# 327final.net
KiCad netlist of a schematic drawn in EAGLE
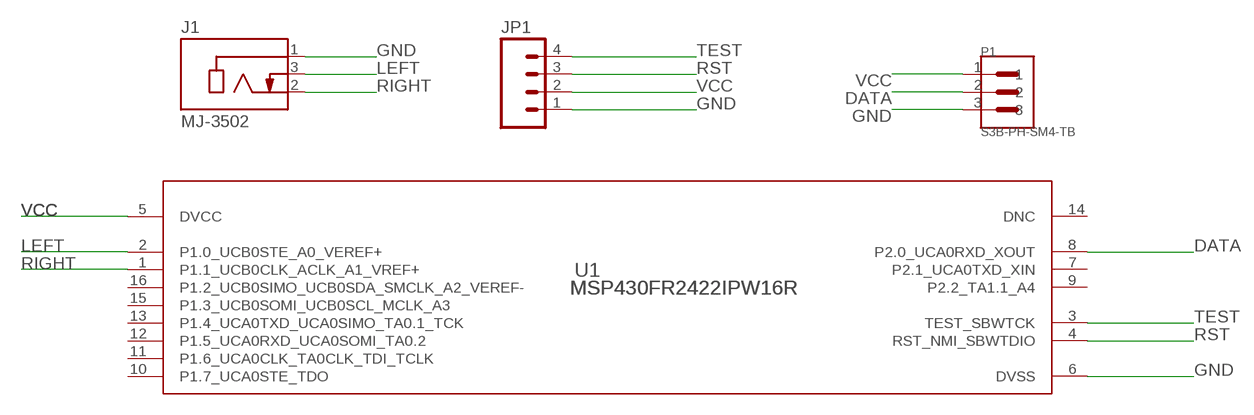
[diagram p0: schematic, sheet 1]

(export (version "E")
  (design (tool "Eeschema 10.0.6"))
  (components
    (comp (ref "J1")
      (value "MJ-3502")
      (footprint "eagle-import:CUI_MJ-3502")
      (fields (field (name "MANUFACTURER") "CUI INC"))
      (libsource (lib "eagle-import") (part "MJ-3502"))
    )
    (comp (ref "JP1")
      (value "HEADER_1X04LOCK")
      (footprint "eagle-import:1X04_LOCK")
      (libsource (lib "eagle-import") (part "HEADER_1X04LOCK"))
    )
    (comp (ref "P1")
      (value "S3B-PH-SM4-TB")
      (footprint "eagle-import:JST_S3B-PH-SM4-TB")
      (fields (field (name "MF") "JST"))
      (libsource (lib "eagle-import") (part "S3B-PH-SM4-TB"))
    )
    (comp (ref "U1")
      (value "MSP430FR2422IPW16R")
      (footprint "eagle-import:PW0016A_N")
      (fields (field (name "COPYRIGHT") "Copyright (C) 2023 Ultra Librarian. All rights reserved."))
      (libsource (lib "eagle-import") (part "MSP430FR2422IPW16R"))
    )
  )
  (nets
    (net (code "1") (name "/DATA") (class "Default")
      (node (ref "P1") (pin "2") (pinfunction "2_2") (pintype "passive"))
      (node (ref "U1") (pin "8") (pinfunction "P2.0_UCA0RXD_XOUT_8") (pintype "bidirectional"))
    )
    (net (code "2") (name "/DNC") (class "Default")
      (node (ref "U1") (pin "14") (pinfunction "DNC_14") (pintype "power_in"))
    )
    (net (code "3") (name "/GND") (class "Default")
      (node (ref "J1") (pin "1") (pinfunction "1_1") (pintype "passive"))
      (node (ref "JP1") (pin "1") (pinfunction "1_1") (pintype "passive"))
      (node (ref "P1") (pin "3") (pinfunction "3_3") (pintype "passive"))
      (node (ref "U1") (pin "6") (pinfunction "DVSS_6") (pintype "power_in"))
    )
    (net (code "4") (name "/LEFT") (class "Default")
      (node (ref "J1") (pin "3") (pinfunction "3_3") (pintype "passive"))
      (node (ref "U1") (pin "2") (pinfunction "P1.0_UCB0STE_A0_VEREF+_2") (pintype "bidirectional"))
    )
    (net (code "5") (name "/RIGHT") (class "Default")
      (node (ref "J1") (pin "2") (pinfunction "2_2") (pintype "passive"))
      (node (ref "U1") (pin "1") (pinfunction "P1.1_UCB0CLK_ACLK_A1_VREF+_1") (pintype "bidirectional"))
    )
    (net (code "6") (name "/RST") (class "Default")
      (node (ref "JP1") (pin "3") (pinfunction "3_3") (pintype "passive"))
      (node (ref "U1") (pin "4") (pinfunction "RST_NMI_SBWTDIO_4") (pintype "bidirectional"))
    )
    (net (code "7") (name "/TEST") (class "Default")
      (node (ref "JP1") (pin "4") (pinfunction "4_4") (pintype "passive"))
      (node (ref "U1") (pin "3") (pinfunction "TEST_SBWTCK_3") (pintype "input"))
    )
    (net (code "8") (name "/VCC") (class "Default")
      (node (ref "JP1") (pin "2") (pinfunction "2_2") (pintype "passive"))
      (node (ref "P1") (pin "1") (pinfunction "1_1") (pintype "passive"))
      (node (ref "U1") (pin "5") (pinfunction "DVCC_5") (pintype "power_in"))
    )
    (net (code "9") (name "unconnected-(U1-P1.2_UCB0SIMO_UCB0SDA_SMCLK_A2_VEREF--Pad16)") (class "Default")
      (node (ref "U1") (pin "16") (pinfunction "P1.2_UCB0SIMO_UCB0SDA_SMCLK_A2_VEREF-_16") (pintype "bidirectional"))
    )
    (net (code "10") (name "unconnected-(U1-P1.3_UCB0SOMI_UCB0SCL_MCLK_A3-Pad15)") (class "Default")
      (node (ref "U1") (pin "15") (pinfunction "P1.3_UCB0SOMI_UCB0SCL_MCLK_A3_15") (pintype "bidirectional"))
    )
    (net (code "11") (name "unconnected-(U1-P1.4_UCA0TXD_UCA0SIMO_TA0.1_TCK-Pad13)") (class "Default")
      (node (ref "U1") (pin "13") (pinfunction "P1.4_UCA0TXD_UCA0SIMO_TA0.1_TCK_13") (pintype "bidirectional"))
    )
    (net (code "12") (name "unconnected-(U1-P1.5_UCA0RXD_UCA0SOMI_TA0.2-Pad12)") (class "Default")
      (node (ref "U1") (pin "12") (pinfunction "P1.5_UCA0RXD_UCA0SOMI_TA0.2_12") (pintype "bidirectional"))
    )
    (net (code "13") (name "unconnected-(U1-P1.6_UCA0CLK_TA0CLK_TDI_TCLK-Pad11)") (class "Default")
      (node (ref "U1") (pin "11") (pinfunction "P1.6_UCA0CLK_TA0CLK_TDI_TCLK_11") (pintype "bidirectional"))
    )
    (net (code "14") (name "unconnected-(U1-P1.7_UCA0STE_TDO-Pad10)") (class "Default")
      (node (ref "U1") (pin "10") (pinfunction "P1.7_UCA0STE_TDO_10") (pintype "bidirectional"))
    )
    (net (code "15") (name "unconnected-(U1-P2.1_UCA0TXD_XIN-Pad7)") (class "Default")
      (node (ref "U1") (pin "7") (pinfunction "P2.1_UCA0TXD_XIN_7") (pintype "bidirectional"))
    )
    (net (code "16") (name "unconnected-(U1-P2.2_TA1.1_A4-Pad9)") (class "Default")
      (node (ref "U1") (pin "9") (pinfunction "P2.2_TA1.1_A4_9") (pintype "bidirectional"))
    )
  )
)
